# Button_Sequencer_single.net
KiCad netlist of a schematic drawn in EAGLE
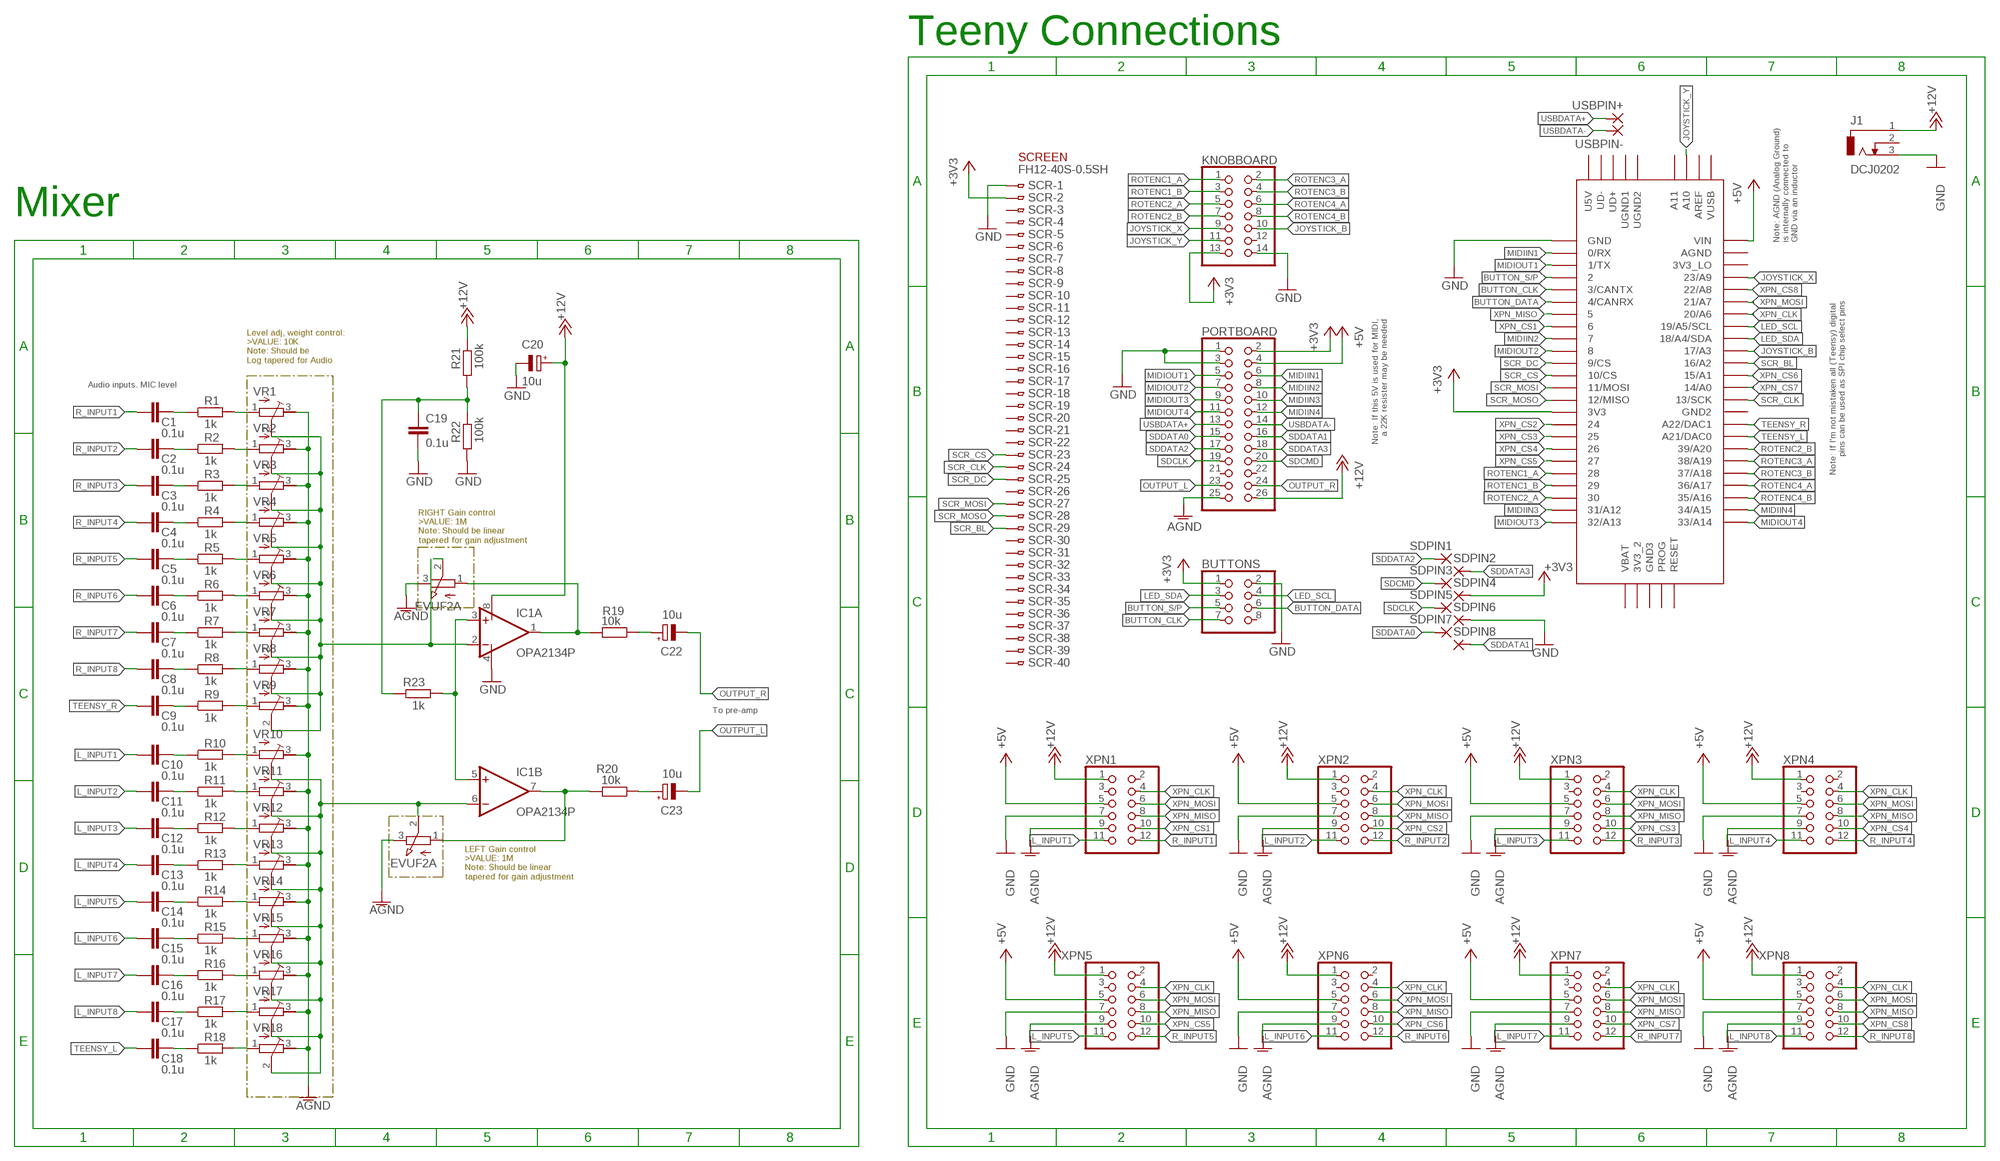
[diagram p0: schematic, sheet 1]

(export (version "E")
  (design (tool "Eeschema 10.0.6"))
  (components
    (comp (ref "BUTTONS")
      (value "PINHD-2X4")
      (footprint "eagle-import:2X04")
      (libsource (lib "eagle-import") (part "PINHD-2X4"))
    )
    (comp (ref "C1")
      (value "0.1u")
      (footprint "eagle-import:C025-030X050")
      (libsource (lib "eagle-import") (part "C-EU025-030X050"))
    )
    (comp (ref "C2")
      (value "0.1u")
      (footprint "eagle-import:C025-030X050")
      (libsource (lib "eagle-import") (part "C-EU025-030X050"))
    )
    (comp (ref "C3")
      (value "0.1u")
      (footprint "eagle-import:C025-030X050")
      (libsource (lib "eagle-import") (part "C-EU025-030X050"))
    )
    (comp (ref "C4")
      (value "0.1u")
      (footprint "eagle-import:C025-030X050")
      (libsource (lib "eagle-import") (part "C-EU025-030X050"))
    )
    (comp (ref "C5")
      (value "0.1u")
      (footprint "eagle-import:C025-030X050")
      (libsource (lib "eagle-import") (part "C-EU025-030X050"))
    )
    (comp (ref "C6")
      (value "0.1u")
      (footprint "eagle-import:C025-030X050")
      (libsource (lib "eagle-import") (part "C-EU025-030X050"))
    )
    (comp (ref "C7")
      (value "0.1u")
      (footprint "eagle-import:C025-030X050")
      (libsource (lib "eagle-import") (part "C-EU025-030X050"))
    )
    (comp (ref "C8")
      (value "0.1u")
      (footprint "eagle-import:C025-030X050")
      (libsource (lib "eagle-import") (part "C-EU025-030X050"))
    )
    (comp (ref "C9")
      (value "0.1u")
      (footprint "eagle-import:C025-030X050")
      (libsource (lib "eagle-import") (part "C-EU025-030X050"))
    )
    (comp (ref "C10")
      (value "0.1u")
      (footprint "eagle-import:C025-030X050")
      (libsource (lib "eagle-import") (part "C-EU025-030X050"))
    )
    (comp (ref "C11")
      (value "0.1u")
      (footprint "eagle-import:C025-030X050")
      (libsource (lib "eagle-import") (part "C-EU025-030X050"))
    )
    (comp (ref "C12")
      (value "0.1u")
      (footprint "eagle-import:C025-030X050")
      (libsource (lib "eagle-import") (part "C-EU025-030X050"))
    )
    (comp (ref "C13")
      (value "0.1u")
      (footprint "eagle-import:C025-030X050")
      (libsource (lib "eagle-import") (part "C-EU025-030X050"))
    )
    (comp (ref "C14")
      (value "0.1u")
      (footprint "eagle-import:C025-030X050")
      (libsource (lib "eagle-import") (part "C-EU025-030X050"))
    )
    (comp (ref "C15")
      (value "0.1u")
      (footprint "eagle-import:C025-030X050")
      (libsource (lib "eagle-import") (part "C-EU025-030X050"))
    )
    (comp (ref "C16")
      (value "0.1u")
      (footprint "eagle-import:C025-030X050")
      (libsource (lib "eagle-import") (part "C-EU025-030X050"))
    )
    (comp (ref "C17")
      (value "0.1u")
      (footprint "eagle-import:C025-030X050")
      (libsource (lib "eagle-import") (part "C-EU025-030X050"))
    )
    (comp (ref "C18")
      (value "0.1u")
      (footprint "eagle-import:C025-030X050")
      (libsource (lib "eagle-import") (part "C-EU025-030X050"))
    )
    (comp (ref "C19")
      (value "0.1u")
      (footprint "eagle-import:C0805")
      (libsource (lib "eagle-import") (part "C-EUC0805"))
    )
    (comp (ref "C20")
      (value "10u")
      (footprint "eagle-import:E5-10,5")
      (libsource (lib "eagle-import") (part "CPOL-EUE5-10.5"))
    )
    (comp (ref "C22")
      (value "10u")
      (footprint "eagle-import:E5-10,5")
      (libsource (lib "eagle-import") (part "CPOL-EUE5-10.5"))
    )
    (comp (ref "C23")
      (value "10u")
      (footprint "eagle-import:E5-10,5")
      (libsource (lib "eagle-import") (part "CPOL-EUE5-10.5"))
    )
    (comp (ref "IC1")
      (value "OPA2134P")
      (footprint "eagle-import:DIL08")
      (libsource (lib "eagle-import") (part "OPA2134P"))
    )
    (comp (ref "J1")
      (value "DCJ0202")
      (footprint "eagle-import:DCJ0202")
      (libsource (lib "eagle-import") (part "DCJ0202"))
    )
    (comp (ref "KNOBBOARD")
      (value "PINHD-2X7")
      (footprint "eagle-import:2X07")
      (libsource (lib "eagle-import") (part "PINHD-2X7"))
    )
    (comp (ref "PORTBOARD")
      (value "PINHD-2X13")
      (footprint "eagle-import:2X13")
      (libsource (lib "eagle-import") (part "PINHD-2X13"))
    )
    (comp (ref "R1")
      (value "1k")
      (footprint "eagle-import:R0805")
      (libsource (lib "eagle-import") (part "R-EU_R0805"))
    )
    (comp (ref "R2")
      (value "1k")
      (footprint "eagle-import:R0805")
      (libsource (lib "eagle-import") (part "R-EU_R0805"))
    )
    (comp (ref "R3")
      (value "1k")
      (footprint "eagle-import:R0805")
      (libsource (lib "eagle-import") (part "R-EU_R0805"))
    )
    (comp (ref "R4")
      (value "1k")
      (footprint "eagle-import:R0805")
      (libsource (lib "eagle-import") (part "R-EU_R0805"))
    )
    (comp (ref "R5")
      (value "1k")
      (footprint "eagle-import:R0805")
      (libsource (lib "eagle-import") (part "R-EU_R0805"))
    )
    (comp (ref "R6")
      (value "1k")
      (footprint "eagle-import:R0805")
      (libsource (lib "eagle-import") (part "R-EU_R0805"))
    )
    (comp (ref "R7")
      (value "1k")
      (footprint "eagle-import:R0805")
      (libsource (lib "eagle-import") (part "R-EU_R0805"))
    )
    (comp (ref "R8")
      (value "1k")
      (footprint "eagle-import:R0805")
      (libsource (lib "eagle-import") (part "R-EU_R0805"))
    )
    (comp (ref "R9")
      (value "1k")
      (footprint "eagle-import:R0805")
      (libsource (lib "eagle-import") (part "R-EU_R0805"))
    )
    (comp (ref "R10")
      (value "1k")
      (footprint "eagle-import:R0805")
      (libsource (lib "eagle-import") (part "R-EU_R0805"))
    )
    (comp (ref "R11")
      (value "1k")
      (footprint "eagle-import:R0805")
      (libsource (lib "eagle-import") (part "R-EU_R0805"))
    )
    (comp (ref "R12")
      (value "1k")
      (footprint "eagle-import:R0805")
      (libsource (lib "eagle-import") (part "R-EU_R0805"))
    )
    (comp (ref "R13")
      (value "1k")
      (footprint "eagle-import:R0805")
      (libsource (lib "eagle-import") (part "R-EU_R0805"))
    )
    (comp (ref "R14")
      (value "1k")
      (footprint "eagle-import:R0805")
      (libsource (lib "eagle-import") (part "R-EU_R0805"))
    )
    (comp (ref "R15")
      (value "1k")
      (footprint "eagle-import:R0805")
      (libsource (lib "eagle-import") (part "R-EU_R0805"))
    )
    (comp (ref "R16")
      (value "1k")
      (footprint "eagle-import:R0805")
      (libsource (lib "eagle-import") (part "R-EU_R0805"))
    )
    (comp (ref "R17")
      (value "1k")
      (footprint "eagle-import:R0805")
      (libsource (lib "eagle-import") (part "R-EU_R0805"))
    )
    (comp (ref "R18")
      (value "1k")
      (footprint "eagle-import:R0805")
      (libsource (lib "eagle-import") (part "R-EU_R0805"))
    )
    (comp (ref "R19")
      (value "10k")
      (footprint "eagle-import:R0805")
      (libsource (lib "eagle-import") (part "R-EU_R0805"))
    )
    (comp (ref "R20")
      (value "10k")
      (footprint "eagle-import:R0805")
      (libsource (lib "eagle-import") (part "R-EU_R0805"))
    )
    (comp (ref "R21")
      (value "100k")
      (footprint "eagle-import:R0805")
      (libsource (lib "eagle-import") (part "R-EU_R0805"))
    )
    (comp (ref "R22")
      (value "100k")
      (footprint "eagle-import:R0805")
      (libsource (lib "eagle-import") (part "R-EU_R0805"))
    )
    (comp (ref "R23")
      (value "1k")
      (footprint "eagle-import:R0805")
      (libsource (lib "eagle-import") (part "R-EU_R0805"))
    )
    (comp (ref "SCR")
      (value "FH12-40S-0.5SH")
      (footprint "eagle-import:FH12-40S-0.5SH")
      (fields (field (name "MPN") "FH12-40S-0.5SH(55)"))
      (libsource (lib "eagle-import") (part "FH12-40S-0.5SH"))
    )
    (comp (ref "SDPIN1")
      (value "1,6/0,8")
      (footprint "eagle-import:1,6_0,8")
      (libsource (lib "eagle-import") (part "1,6/0,8"))
    )
    (comp (ref "SDPIN2")
      (value "1,6/0,8")
      (footprint "eagle-import:1,6_0,8")
      (libsource (lib "eagle-import") (part "1,6/0,8"))
    )
    (comp (ref "SDPIN3")
      (value "1,6/0,8")
      (footprint "eagle-import:1,6_0,8")
      (libsource (lib "eagle-import") (part "1,6/0,8"))
    )
    (comp (ref "SDPIN4")
      (value "1,6/0,8")
      (footprint "eagle-import:1,6_0,8")
      (libsource (lib "eagle-import") (part "1,6/0,8"))
    )
    (comp (ref "SDPIN5")
      (value "1,6/0,8")
      (footprint "eagle-import:1,6_0,8")
      (libsource (lib "eagle-import") (part "1,6/0,8"))
    )
    (comp (ref "SDPIN6")
      (value "1,6/0,8")
      (footprint "eagle-import:1,6_0,8")
      (libsource (lib "eagle-import") (part "1,6/0,8"))
    )
    (comp (ref "SDPIN7")
      (value "1,6/0,8")
      (footprint "eagle-import:1,6_0,8")
      (libsource (lib "eagle-import") (part "1,6/0,8"))
    )
    (comp (ref "SDPIN8")
      (value "1,6/0,8")
      (footprint "eagle-import:1,6_0,8")
      (libsource (lib "eagle-import") (part "1,6/0,8"))
    )
    (comp (ref "TEENSY_3.6")
      (value "TEENSY_3.5/3.6")
      (footprint "eagle-import:TEENSY_3.5_3.6")
      (libsource (lib "eagle-import") (part "TEENSY_3.5/3.6"))
    )
    (comp (ref "USBPIN+")
      (value "1,6/0,8")
      (footprint "eagle-import:1,6_0,8")
      (libsource (lib "eagle-import") (part "1,6/0,8"))
    )
    (comp (ref "USBPIN-")
      (value "1,6/0,8")
      (footprint "eagle-import:1,6_0,8")
      (libsource (lib "eagle-import") (part "1,6/0,8"))
    )
    (comp (ref "VR1")
      (value "R-TRIMM3339P")
      (footprint "eagle-import:RTRIM3339P")
      (libsource (lib "eagle-import") (part "R-TRIMM3339P"))
    )
    (comp (ref "VR2")
      (value "R-TRIMM3339P")
      (footprint "eagle-import:RTRIM3339P")
      (libsource (lib "eagle-import") (part "R-TRIMM3339P"))
    )
    (comp (ref "VR3")
      (value "R-TRIMM3339P")
      (footprint "eagle-import:RTRIM3339P")
      (libsource (lib "eagle-import") (part "R-TRIMM3339P"))
    )
    (comp (ref "VR4")
      (value "R-TRIMM3339P")
      (footprint "eagle-import:RTRIM3339P")
      (libsource (lib "eagle-import") (part "R-TRIMM3339P"))
    )
    (comp (ref "VR5")
      (value "R-TRIMM3339P")
      (footprint "eagle-import:RTRIM3339P")
      (libsource (lib "eagle-import") (part "R-TRIMM3339P"))
    )
    (comp (ref "VR6")
      (value "R-TRIMM3339P")
      (footprint "eagle-import:RTRIM3339P")
      (libsource (lib "eagle-import") (part "R-TRIMM3339P"))
    )
    (comp (ref "VR7")
      (value "R-TRIMM3339P")
      (footprint "eagle-import:RTRIM3339P")
      (libsource (lib "eagle-import") (part "R-TRIMM3339P"))
    )
    (comp (ref "VR8")
      (value "R-TRIMM3339P")
      (footprint "eagle-import:RTRIM3339P")
      (libsource (lib "eagle-import") (part "R-TRIMM3339P"))
    )
    (comp (ref "VR9")
      (value "R-TRIMM3339P")
      (footprint "eagle-import:RTRIM3339P")
      (libsource (lib "eagle-import") (part "R-TRIMM3339P"))
    )
    (comp (ref "VR10")
      (value "R-TRIMM3339P")
      (footprint "eagle-import:RTRIM3339P")
      (libsource (lib "eagle-import") (part "R-TRIMM3339P"))
    )
    (comp (ref "VR11")
      (value "R-TRIMM3339P")
      (footprint "eagle-import:RTRIM3339P")
      (libsource (lib "eagle-import") (part "R-TRIMM3339P"))
    )
    (comp (ref "VR12")
      (value "R-TRIMM3339P")
      (footprint "eagle-import:RTRIM3339P")
      (libsource (lib "eagle-import") (part "R-TRIMM3339P"))
    )
    (comp (ref "VR13")
      (value "R-TRIMM3339P")
      (footprint "eagle-import:RTRIM3339P")
      (libsource (lib "eagle-import") (part "R-TRIMM3339P"))
    )
    (comp (ref "VR14")
      (value "R-TRIMM3339P")
      (footprint "eagle-import:RTRIM3339P")
      (libsource (lib "eagle-import") (part "R-TRIMM3339P"))
    )
    (comp (ref "VR15")
      (value "R-TRIMM3339P")
      (footprint "eagle-import:RTRIM3339P")
      (libsource (lib "eagle-import") (part "R-TRIMM3339P"))
    )
    (comp (ref "VR16")
      (value "R-TRIMM3339P")
      (footprint "eagle-import:RTRIM3339P")
      (libsource (lib "eagle-import") (part "R-TRIMM3339P"))
    )
    (comp (ref "VR17")
      (value "R-TRIMM3339P")
      (footprint "eagle-import:RTRIM3339P")
      (libsource (lib "eagle-import") (part "R-TRIMM3339P"))
    )
    (comp (ref "VR18")
      (value "R-TRIMM3339P")
      (footprint "eagle-import:RTRIM3339P")
      (libsource (lib "eagle-import") (part "R-TRIMM3339P"))
    )
    (comp (ref "VR19")
      (value "EVUF2A")
      (footprint "eagle-import:EVUF")
      (libsource (lib "eagle-import") (part "EVUAF2"))
    )
    (comp (ref "VR20")
      (value "EVUF2A")
      (footprint "eagle-import:EVUF")
      (libsource (lib "eagle-import") (part "EVUAF2"))
    )
    (comp (ref "XPN1")
      (value "PINHD-2X6")
      (footprint "eagle-import:2X06")
      (libsource (lib "eagle-import") (part "PINHD-2X6"))
    )
    (comp (ref "XPN2")
      (value "PINHD-2X6")
      (footprint "eagle-import:2X06")
      (libsource (lib "eagle-import") (part "PINHD-2X6"))
    )
    (comp (ref "XPN3")
      (value "PINHD-2X6")
      (footprint "eagle-import:2X06")
      (libsource (lib "eagle-import") (part "PINHD-2X6"))
    )
    (comp (ref "XPN4")
      (value "PINHD-2X6")
      (footprint "eagle-import:2X06")
      (libsource (lib "eagle-import") (part "PINHD-2X6"))
    )
    (comp (ref "XPN5")
      (value "PINHD-2X6")
      (footprint "eagle-import:2X06")
      (libsource (lib "eagle-import") (part "PINHD-2X6"))
    )
    (comp (ref "XPN6")
      (value "PINHD-2X6")
      (footprint "eagle-import:2X06")
      (libsource (lib "eagle-import") (part "PINHD-2X6"))
    )
    (comp (ref "XPN7")
      (value "PINHD-2X6")
      (footprint "eagle-import:2X06")
      (libsource (lib "eagle-import") (part "PINHD-2X6"))
    )
    (comp (ref "XPN8")
      (value "PINHD-2X6")
      (footprint "eagle-import:2X06")
      (libsource (lib "eagle-import") (part "PINHD-2X6"))
    )
  )
  (nets
    (net (code "1") (name "+3V3") (class "Default")
      (node (ref "BUTTONS") (pin "1") (pinfunction "1_1") (pintype "passive"))
      (node (ref "KNOBBOARD") (pin "13") (pinfunction "13_13") (pintype "passive"))
      (node (ref "PORTBOARD") (pin "2") (pinfunction "2_2") (pintype "passive"))
      (node (ref "SCR") (pin "2") (pinfunction "1_2") (pintype "passive"))
      (node (ref "SDPIN4") (pin "1") (pinfunction "P_1") (pintype "passive"))
      (node (ref "TEENSY_3.6") (pin "3V3") (pinfunction "3V3_3V3") (pintype "bidirectional"))
    )
    (net (code "2") (name "+5V") (class "Default")
      (node (ref "PORTBOARD") (pin "4") (pinfunction "4_4") (pintype "passive"))
      (node (ref "TEENSY_3.6") (pin "VIN") (pinfunction "VIN_VIN") (pintype "bidirectional"))
      (node (ref "XPN1") (pin "5") (pinfunction "5_5") (pintype "passive"))
      (node (ref "XPN2") (pin "5") (pinfunction "5_5") (pintype "passive"))
      (node (ref "XPN3") (pin "5") (pinfunction "5_5") (pintype "passive"))
      (node (ref "XPN4") (pin "5") (pinfunction "5_5") (pintype "passive"))
      (node (ref "XPN5") (pin "5") (pinfunction "5_5") (pintype "passive"))
      (node (ref "XPN6") (pin "5") (pinfunction "5_5") (pintype "passive"))
      (node (ref "XPN7") (pin "5") (pinfunction "5_5") (pintype "passive"))
      (node (ref "XPN8") (pin "5") (pinfunction "5_5") (pintype "passive"))
    )
    (net (code "3") (name "+12V") (class "Default")
      (node (ref "C20") (pin "+") (pinfunction "+_+") (pintype "passive"))
      (node (ref "IC1") (pin "8") (pinfunction "V+_8") (pintype "power_in"))
      (node (ref "J1") (pin "1") (pinfunction "1_1") (pintype "passive"))
      (node (ref "PORTBOARD") (pin "26") (pinfunction "26_26") (pintype "passive"))
      (node (ref "R21") (pin "2") (pinfunction "2_2") (pintype "passive"))
      (node (ref "XPN1") (pin "1") (pinfunction "1_1") (pintype "passive"))
      (node (ref "XPN2") (pin "1") (pinfunction "1_1") (pintype "passive"))
      (node (ref "XPN3") (pin "1") (pinfunction "1_1") (pintype "passive"))
      (node (ref "XPN4") (pin "1") (pinfunction "1_1") (pintype "passive"))
      (node (ref "XPN5") (pin "1") (pinfunction "1_1") (pintype "passive"))
      (node (ref "XPN6") (pin "1") (pinfunction "1_1") (pintype "passive"))
      (node (ref "XPN7") (pin "1") (pinfunction "1_1") (pintype "passive"))
      (node (ref "XPN8") (pin "1") (pinfunction "1_1") (pintype "passive"))
    )
    (net (code "4") (name "AGND") (class "Default")
      (node (ref "PORTBOARD") (pin "25") (pinfunction "25_25") (pintype "passive"))
      (node (ref "VR1") (pin "3") (pinfunction "E_3") (pintype "passive"))
      (node (ref "VR10") (pin "3") (pinfunction "E_3") (pintype "passive"))
      (node (ref "VR11") (pin "3") (pinfunction "E_3") (pintype "passive"))
      (node (ref "VR12") (pin "3") (pinfunction "E_3") (pintype "passive"))
      (node (ref "VR13") (pin "3") (pinfunction "E_3") (pintype "passive"))
      (node (ref "VR14") (pin "3") (pinfunction "E_3") (pintype "passive"))
      (node (ref "VR15") (pin "3") (pinfunction "E_3") (pintype "passive"))
      (node (ref "VR16") (pin "3") (pinfunction "E_3") (pintype "passive"))
      (node (ref "VR17") (pin "3") (pinfunction "E_3") (pintype "passive"))
      (node (ref "VR18") (pin "3") (pinfunction "E_3") (pintype "passive"))
      (node (ref "VR19") (pin "3") (pinfunction "E_3") (pintype "passive"))
      (node (ref "VR2") (pin "3") (pinfunction "E_3") (pintype "passive"))
      (node (ref "VR20") (pin "3") (pinfunction "E_3") (pintype "passive"))
      (node (ref "VR3") (pin "3") (pinfunction "E_3") (pintype "passive"))
      (node (ref "VR4") (pin "3") (pinfunction "E_3") (pintype "passive"))
      (node (ref "VR5") (pin "3") (pinfunction "E_3") (pintype "passive"))
      (node (ref "VR6") (pin "3") (pinfunction "E_3") (pintype "passive"))
      (node (ref "VR7") (pin "3") (pinfunction "E_3") (pintype "passive"))
      (node (ref "VR8") (pin "3") (pinfunction "E_3") (pintype "passive"))
      (node (ref "VR9") (pin "3") (pinfunction "E_3") (pintype "passive"))
      (node (ref "XPN1") (pin "9") (pinfunction "9_9") (pintype "passive"))
      (node (ref "XPN2") (pin "9") (pinfunction "9_9") (pintype "passive"))
      (node (ref "XPN3") (pin "9") (pinfunction "9_9") (pintype "passive"))
      (node (ref "XPN4") (pin "9") (pinfunction "9_9") (pintype "passive"))
      (node (ref "XPN5") (pin "9") (pinfunction "9_9") (pintype "passive"))
      (node (ref "XPN6") (pin "9") (pinfunction "9_9") (pintype "passive"))
      (node (ref "XPN7") (pin "9") (pinfunction "9_9") (pintype "passive"))
      (node (ref "XPN8") (pin "9") (pinfunction "9_9") (pintype "passive"))
    )
    (net (code "5") (name "BUTTON_CLK") (class "Default")
      (node (ref "BUTTONS") (pin "7") (pinfunction "7_7") (pintype "passive"))
      (node (ref "TEENSY_3.6") (pin "3/CANTX") (pinfunction "3/CANTX_3/CANTX") (pintype "bidirectional"))
    )
    (net (code "6") (name "BUTTON_DATA") (class "Default")
      (node (ref "BUTTONS") (pin "6") (pinfunction "6_6") (pintype "passive"))
      (node (ref "TEENSY_3.6") (pin "4/CANRX") (pinfunction "4/CANRX_4/CANRX") (pintype "bidirectional"))
    )
    (net (code "7") (name "BUTTON_S{slash}P") (class "Default")
      (node (ref "BUTTONS") (pin "5") (pinfunction "5_5") (pintype "passive"))
      (node (ref "TEENSY_3.6") (pin "2") (pinfunction "2_2") (pintype "bidirectional"))
    )
    (net (code "8") (name "GND") (class "Default")
      (node (ref "BUTTONS") (pin "2") (pinfunction "2_2") (pintype "passive"))
      (node (ref "C19") (pin "2") (pinfunction "2_2") (pintype "passive"))
      (node (ref "C20") (pin "-") (pinfunction "-_-") (pintype "passive"))
      (node (ref "IC1") (pin "4") (pinfunction "V-_4") (pintype "power_in"))
      (node (ref "J1") (pin "3") (pinfunction "3_3") (pintype "passive"))
      (node (ref "KNOBBOARD") (pin "14") (pinfunction "14_14") (pintype "passive"))
      (node (ref "PORTBOARD") (pin "1") (pinfunction "1_1") (pintype "passive"))
      (node (ref "PORTBOARD") (pin "3") (pinfunction "3_3") (pintype "passive"))
      (node (ref "R22") (pin "1") (pinfunction "1_1") (pintype "passive"))
      (node (ref "SCR") (pin "1") (pinfunction "1_1") (pintype "passive"))
      (node (ref "SDPIN6") (pin "1") (pinfunction "P_1") (pintype "passive"))
      (node (ref "TEENSY_3.6") (pin "GND") (pinfunction "GND_GND") (pintype "bidirectional"))
      (node (ref "XPN1") (pin "7") (pinfunction "7_7") (pintype "passive"))
      (node (ref "XPN2") (pin "7") (pinfunction "7_7") (pintype "passive"))
      (node (ref "XPN3") (pin "7") (pinfunction "7_7") (pintype "passive"))
      (node (ref "XPN4") (pin "7") (pinfunction "7_7") (pintype "passive"))
      (node (ref "XPN5") (pin "7") (pinfunction "7_7") (pintype "passive"))
      (node (ref "XPN6") (pin "7") (pinfunction "7_7") (pintype "passive"))
      (node (ref "XPN7") (pin "7") (pinfunction "7_7") (pintype "passive"))
      (node (ref "XPN8") (pin "7") (pinfunction "7_7") (pintype "passive"))
    )
    (net (code "9") (name "JOYSTICK_B") (class "Default")
      (node (ref "KNOBBOARD") (pin "10") (pinfunction "10_10") (pintype "passive"))
      (node (ref "TEENSY_3.6") (pin "17/A3") (pinfunction "17/A3_17/A3") (pintype "bidirectional"))
    )
    (net (code "10") (name "JOYSTICK_X") (class "Default")
      (node (ref "KNOBBOARD") (pin "9") (pinfunction "9_9") (pintype "passive"))
      (node (ref "TEENSY_3.6") (pin "23/A9") (pinfunction "23/A9_23/A9") (pintype "bidirectional"))
    )
    (net (code "11") (name "JOYSTICK_Y") (class "Default")
      (node (ref "KNOBBOARD") (pin "11") (pinfunction "11_11") (pintype "passive"))
      (node (ref "TEENSY_3.6") (pin "A10") (pinfunction "A10_A10") (pintype "bidirectional"))
    )
    (net (code "12") (name "LED_SCL") (class "Default")
      (node (ref "BUTTONS") (pin "4") (pinfunction "4_4") (pintype "passive"))
      (node (ref "TEENSY_3.6") (pin "19/A5/SCL") (pinfunction "19/A5/SCL_19/A5/SCL") (pintype "bidirectional"))
    )
    (net (code "13") (name "LED_SDA") (class "Default")
      (node (ref "BUTTONS") (pin "3") (pinfunction "3_3") (pintype "passive"))
      (node (ref "TEENSY_3.6") (pin "18/A4/SDA") (pinfunction "18/A4/SDA_18/A4/SDA") (pintype "bidirectional"))
    )
    (net (code "14") (name "L_INPUT1") (class "Default")
      (node (ref "C10") (pin "2") (pinfunction "2_2") (pintype "passive"))
      (node (ref "XPN1") (pin "11") (pinfunction "11_11") (pintype "passive"))
    )
    (net (code "15") (name "L_INPUT2") (class "Default")
      (node (ref "C11") (pin "2") (pinfunction "2_2") (pintype "passive"))
      (node (ref "XPN2") (pin "11") (pinfunction "11_11") (pintype "passive"))
    )
    (net (code "16") (name "L_INPUT3") (class "Default")
      (node (ref "C12") (pin "2") (pinfunction "2_2") (pintype "passive"))
      (node (ref "XPN3") (pin "11") (pinfunction "11_11") (pintype "passive"))
    )
    (net (code "17") (name "L_INPUT4") (class "Default")
      (node (ref "C13") (pin "2") (pinfunction "2_2") (pintype "passive"))
      (node (ref "XPN4") (pin "11") (pinfunction "11_11") (pintype "passive"))
    )
    (net (code "18") (name "L_INPUT5") (class "Default")
      (node (ref "C14") (pin "2") (pinfunction "2_2") (pintype "passive"))
      (node (ref "XPN5") (pin "11") (pinfunction "11_11") (pintype "passive"))
    )
    (net (code "19") (name "L_INPUT6") (class "Default")
      (node (ref "C15") (pin "2") (pinfunction "2_2") (pintype "passive"))
      (node (ref "XPN6") (pin "11") (pinfunction "11_11") (pintype "passive"))
    )
    (net (code "20") (name "L_INPUT7") (class "Default")
      (node (ref "C16") (pin "2") (pinfunction "2_2") (pintype "passive"))
      (node (ref "XPN7") (pin "11") (pinfunction "11_11") (pintype "passive"))
    )
    (net (code "21") (name "L_INPUT8") (class "Default")
      (node (ref "C17") (pin "2") (pinfunction "2_2") (pintype "passive"))
      (node (ref "XPN8") (pin "11") (pinfunction "11_11") (pintype "passive"))
    )
    (net (code "22") (name "MIDIIN1") (class "Default")
      (node (ref "PORTBOARD") (pin "6") (pinfunction "6_6") (pintype "passive"))
      (node (ref "TEENSY_3.6") (pin "0/RX") (pinfunction "0/RX_0/RX") (pintype "bidirectional"))
    )
    (net (code "23") (name "MIDIIN2") (class "Default")
      (node (ref "PORTBOARD") (pin "8") (pinfunction "8_8") (pintype "passive"))
      (node (ref "TEENSY_3.6") (pin "7") (pinfunction "7_7") (pintype "bidirectional"))
    )
    (net (code "24") (name "MIDIIN3") (class "Default")
      (node (ref "PORTBOARD") (pin "10") (pinfunction "10_10") (pintype "passive"))
      (node (ref "TEENSY_3.6") (pin "31/A12") (pinfunction "31/A12_31/A12") (pintype "bidirectional"))
    )
    (net (code "25") (name "MIDIIN4") (class "Default")
      (node (ref "PORTBOARD") (pin "12") (pinfunction "12_12") (pintype "passive"))
      (node (ref "TEENSY_3.6") (pin "34/A15") (pinfunction "34/A15_34/A15") (pintype "bidirectional"))
    )
    (net (code "26") (name "MIDIOUT1") (class "Default")
      (node (ref "PORTBOARD") (pin "5") (pinfunction "5_5") (pintype "passive"))
      (node (ref "TEENSY_3.6") (pin "1/TX") (pinfunction "1/TX_1/TX") (pintype "bidirectional"))
    )
    (net (code "27") (name "MIDIOUT2") (class "Default")
      (node (ref "PORTBOARD") (pin "7") (pinfunction "7_7") (pintype "passive"))
      (node (ref "TEENSY_3.6") (pin "8") (pinfunction "8_8") (pintype "bidirectional"))
    )
    (net (code "28") (name "MIDIOUT3") (class "Default")
      (node (ref "PORTBOARD") (pin "9") (pinfunction "9_9") (pintype "passive"))
      (node (ref "TEENSY_3.6") (pin "32/A13") (pinfunction "32/A13_32/A13") (pintype "bidirectional"))
    )
    (net (code "29") (name "MIDIOUT4") (class "Default")
      (node (ref "PORTBOARD") (pin "11") (pinfunction "11_11") (pintype "passive"))
      (node (ref "TEENSY_3.6") (pin "33/A14") (pinfunction "33/A14_33/A14") (pintype "bidirectional"))
    )
    (net (code "30") (name "Net-(C1-Pad1)") (class "Default")
      (node (ref "C1") (pin "1") (pinfunction "1_1") (pintype "passive"))
      (node (ref "R1") (pin "1") (pinfunction "1_1") (pintype "passive"))
    )
    (net (code "31") (name "Net-(C2-Pad1)") (class "Default")
      (node (ref "C2") (pin "1") (pinfunction "1_1") (pintype "passive"))
      (node (ref "R2") (pin "1") (pinfunction "1_1") (pintype "passive"))
    )
    (net (code "32") (name "Net-(C3-Pad1)") (class "Default")
      (node (ref "C3") (pin "1") (pinfunction "1_1") (pintype "passive"))
      (node (ref "R3") (pin "1") (pinfunction "1_1") (pintype "passive"))
    )
    (net (code "33") (name "Net-(C4-Pad1)") (class "Default")
      (node (ref "C4") (pin "1") (pinfunction "1_1") (pintype "passive"))
      (node (ref "R4") (pin "1") (pinfunction "1_1") (pintype "passive"))
    )
    (net (code "34") (name "Net-(C5-Pad1)") (class "Default")
      (node (ref "C5") (pin "1") (pinfunction "1_1") (pintype "passive"))
      (node (ref "R5") (pin "1") (pinfunction "1_1") (pintype "passive"))
    )
    (net (code "35") (name "Net-(C6-Pad1)") (class "Default")
      (node (ref "C6") (pin "1") (pinfunction "1_1") (pintype "passive"))
      (node (ref "R6") (pin "1") (pinfunction "1_1") (pintype "passive"))
    )
    (net (code "36") (name "Net-(C7-Pad1)") (class "Default")
      (node (ref "C7") (pin "1") (pinfunction "1_1") (pintype "passive"))
      (node (ref "R7") (pin "1") (pinfunction "1_1") (pintype "passive"))
    )
    (net (code "37") (name "Net-(C8-Pad1)") (class "Default")
      (node (ref "C8") (pin "1") (pinfunction "1_1") (pintype "passive"))
      (node (ref "R8") (pin "1") (pinfunction "1_1") (pintype "passive"))
    )
    (net (code "38") (name "Net-(C9-Pad1)") (class "Default")
      (node (ref "C9") (pin "1") (pinfunction "1_1") (pintype "passive"))
      (node (ref "R9") (pin "1") (pinfunction "1_1") (pintype "passive"))
    )
    (net (code "39") (name "Net-(C10-Pad1)") (class "Default")
      (node (ref "C10") (pin "1") (pinfunction "1_1") (pintype "passive"))
      (node (ref "R10") (pin "1") (pinfunction "1_1") (pintype "passive"))
    )
    (net (code "40") (name "Net-(C11-Pad1)") (class "Default")
      (node (ref "C11") (pin "1") (pinfunction "1_1") (pintype "passive"))
      (node (ref "R11") (pin "1") (pinfunction "1_1") (pintype "passive"))
    )
    (net (code "41") (name "Net-(C12-Pad1)") (class "Default")
      (node (ref "C12") (pin "1") (pinfunction "1_1") (pintype "passive"))
      (node (ref "R12") (pin "1") (pinfunction "1_1") (pintype "passive"))
    )
    (net (code "42") (name "Net-(C13-Pad1)") (class "Default")
      (node (ref "C13") (pin "1") (pinfunction "1_1") (pintype "passive"))
      (node (ref "R13") (pin "1") (pinfunction "1_1") (pintype "passive"))
    )
    (net (code "43") (name "Net-(C14-Pad1)") (class "Default")
      (node (ref "C14") (pin "1") (pinfunction "1_1") (pintype "passive"))
      (node (ref "R14") (pin "1") (pinfunction "1_1") (pintype "passive"))
    )
    (net (code "44") (name "Net-(C15-Pad1)") (class "Default")
      (node (ref "C15") (pin "1") (pinfunction "1_1") (pintype "passive"))
      (node (ref "R15") (pin "1") (pinfunction "1_1") (pintype "passive"))
    )
    (net (code "45") (name "Net-(C16-Pad1)") (class "Default")
      (node (ref "C16") (pin "1") (pinfunction "1_1") (pintype "passive"))
      (node (ref "R16") (pin "1") (pinfunction "1_1") (pintype "passive"))
    )
    (net (code "46") (name "Net-(C17-Pad1)") (class "Default")
      (node (ref "C17") (pin "1") (pinfunction "1_1") (pintype "passive"))
      (node (ref "R17") (pin "1") (pinfunction "1_1") (pintype "passive"))
    )
    (net (code "47") (name "Net-(C18-Pad1)") (class "Default")
      (node (ref "C18") (pin "1") (pinfunction "1_1") (pintype "passive"))
      (node (ref "R18") (pin "1") (pinfunction "1_1") (pintype "passive"))
    )
    (net (code "48") (name "Net-(C19-Pad1)") (class "Default")
      (node (ref "C19") (pin "1") (pinfunction "1_1") (pintype "passive"))
      (node (ref "R21") (pin "1") (pinfunction "1_1") (pintype "passive"))
      (node (ref "R22") (pin "2") (pinfunction "2_2") (pintype "passive"))
      (node (ref "R23") (pin "2") (pinfunction "2_2") (pintype "passive"))
    )
    (net (code "49") (name "Net-(C22-Pad+)") (class "Default")
      (node (ref "C22") (pin "+") (pinfunction "+_+") (pintype "passive"))
      (node (ref "R19") (pin "1") (pinfunction "1_1") (pintype "passive"))
    )
    (net (code "50") (name "Net-(C23-Pad+)") (class "Default")
      (node (ref "C23") (pin "+") (pinfunction "+_+") (pintype "passive"))
      (node (ref "R20") (pin "1") (pinfunction "1_1") (pintype "passive"))
    )
    (net (code "51") (name "Net-(IC1A-+IN)") (class "Default")
      (node (ref "IC1") (pin "3") (pinfunction "+IN_3") (pintype "input"))
      (node (ref "IC1") (pin "5") (pinfunction "+IN_5") (pintype "input"))
      (node (ref "R23") (pin "1") (pinfunction "1_1") (pintype "passive"))
    )
    (net (code "52") (name "Net-(IC1A--IN)") (class "Default")
      (node (ref "IC1") (pin "2") (pinfunction "-IN_2") (pintype "input"))
      (node (ref "VR1") (pin "2") (pinfunction "S_2") (pintype "passive"))
      (node (ref "VR19") (pin "2") (pinfunction "S_2") (pintype "passive"))
      (node (ref "VR2") (pin "2") (pinfunction "S_2") (pintype "passive"))
      (node (ref "VR3") (pin "2") (pinfunction "S_2") (pintype "passive"))
      (node (ref "VR4") (pin "2") (pinfunction "S_2") (pintype "passive"))
      (node (ref "VR5") (pin "2") (pinfunction "S_2") (pintype "passive"))
      (node (ref "VR6") (pin "2") (pinfunction "S_2") (pintype "passive"))
      (node (ref "VR7") (pin "2") (pinfunction "S_2") (pintype "passive"))
      (node (ref "VR8") (pin "2") (pinfunction "S_2") (pintype "passive"))
      (node (ref "VR9") (pin "2") (pinfunction "S_2") (pintype "passive"))
    )
    (net (code "53") (name "Net-(IC1A-OUT)") (class "Default")
      (node (ref "IC1") (pin "1") (pinfunction "OUT_1") (pintype "output"))
      (node (ref "R19") (pin "2") (pinfunction "2_2") (pintype "passive"))
      (node (ref "VR19") (pin "1") (pinfunction "A_1") (pintype "passive"))
    )
    (net (code "54") (name "Net-(IC1B--IN)") (class "Default")
      (node (ref "IC1") (pin "6") (pinfunction "-IN_6") (pintype "input"))
      (node (ref "VR10") (pin "2") (pinfunction "S_2") (pintype "passive"))
      (node (ref "VR11") (pin "2") (pinfunction "S_2") (pintype "passive"))
      (node (ref "VR12") (pin "2") (pinfunction "S_2") (pintype "passive"))
      (node (ref "VR13") (pin "2") (pinfunction "S_2") (pintype "passive"))
      (node (ref "VR14") (pin "2") (pinfunction "S_2") (pintype "passive"))
      (node (ref "VR15") (pin "2") (pinfunction "S_2") (pintype "passive"))
      (node (ref "VR16") (pin "2") (pinfunction "S_2") (pintype "passive"))
      (node (ref "VR17") (pin "2") (pinfunction "S_2") (pintype "passive"))
      (node (ref "VR18") (pin "2") (pinfunction "S_2") (pintype "passive"))
      (node (ref "VR20") (pin "2") (pinfunction "S_2") (pintype "passive"))
    )
    (net (code "55") (name "Net-(IC1B-OUT)") (class "Default")
      (node (ref "IC1") (pin "7") (pinfunction "OUT_7") (pintype "output"))
      (node (ref "R20") (pin "2") (pinfunction "2_2") (pintype "passive"))
      (node (ref "VR20") (pin "1") (pinfunction "A_1") (pintype "passive"))
    )
    (net (code "56") (name "Net-(VR1-A)") (class "Default")
      (node (ref "R1") (pin "2") (pinfunction "2_2") (pintype "passive"))
      (node (ref "VR1") (pin "1") (pinfunction "A_1") (pintype "passive"))
    )
    (net (code "57") (name "Net-(VR2-A)") (class "Default")
      (node (ref "R2") (pin "2") (pinfunction "2_2") (pintype "passive"))
      (node (ref "VR2") (pin "1") (pinfunction "A_1") (pintype "passive"))
    )
    (net (code "58") (name "Net-(VR3-A)") (class "Default")
      (node (ref "R3") (pin "2") (pinfunction "2_2") (pintype "passive"))
      (node (ref "VR3") (pin "1") (pinfunction "A_1") (pintype "passive"))
    )
    (net (code "59") (name "Net-(VR4-A)") (class "Default")
      (node (ref "R4") (pin "2") (pinfunction "2_2") (pintype "passive"))
      (node (ref "VR4") (pin "1") (pinfunction "A_1") (pintype "passive"))
    )
    (net (code "60") (name "Net-(VR5-A)") (class "Default")
      (node (ref "R5") (pin "2") (pinfunction "2_2") (pintype "passive"))
      (node (ref "VR5") (pin "1") (pinfunction "A_1") (pintype "passive"))
    )
    (net (code "61") (name "Net-(VR6-A)") (class "Default")
      (node (ref "R6") (pin "2") (pinfunction "2_2") (pintype "passive"))
      (node (ref "VR6") (pin "1") (pinfunction "A_1") (pintype "passive"))
    )
    (net (code "62") (name "Net-(VR7-A)") (class "Default")
      (node (ref "R7") (pin "2") (pinfunction "2_2") (pintype "passive"))
      (node (ref "VR7") (pin "1") (pinfunction "A_1") (pintype "passive"))
    )
    (net (code "63") (name "Net-(VR8-A)") (class "Default")
      (node (ref "R8") (pin "2") (pinfunction "2_2") (pintype "passive"))
      (node (ref "VR8") (pin "1") (pinfunction "A_1") (pintype "passive"))
    )
    (net (code "64") (name "Net-(VR9-A)") (class "Default")
      (node (ref "R9") (pin "2") (pinfunction "2_2") (pintype "passive"))
      (node (ref "VR9") (pin "1") (pinfunction "A_1") (pintype "passive"))
    )
    (net (code "65") (name "Net-(VR10-A)") (class "Default")
      (node (ref "R10") (pin "2") (pinfunction "2_2") (pintype "passive"))
      (node (ref "VR10") (pin "1") (pinfunction "A_1") (pintype "passive"))
    )
    (net (code "66") (name "Net-(VR11-A)") (class "Default")
      (node (ref "R11") (pin "2") (pinfunction "2_2") (pintype "passive"))
      (node (ref "VR11") (pin "1") (pinfunction "A_1") (pintype "passive"))
    )
    (net (code "67") (name "Net-(VR12-A)") (class "Default")
      (node (ref "R12") (pin "2") (pinfunction "2_2") (pintype "passive"))
      (node (ref "VR12") (pin "1") (pinfunction "A_1") (pintype "passive"))
    )
    (net (code "68") (name "Net-(VR13-A)") (class "Default")
      (node (ref "R13") (pin "2") (pinfunction "2_2") (pintype "passive"))
      (node (ref "VR13") (pin "1") (pinfunction "A_1") (pintype "passive"))
    )
    (net (code "69") (name "Net-(VR14-A)") (class "Default")
      (node (ref "R14") (pin "2") (pinfunction "2_2") (pintype "passive"))
      (node (ref "VR14") (pin "1") (pinfunction "A_1") (pintype "passive"))
    )
    (net (code "70") (name "Net-(VR15-A)") (class "Default")
      (node (ref "R15") (pin "2") (pinfunction "2_2") (pintype "passive"))
      (node (ref "VR15") (pin "1") (pinfunction "A_1") (pintype "passive"))
    )
    (net (code "71") (name "Net-(VR16-A)") (class "Default")
      (node (ref "R16") (pin "2") (pinfunction "2_2") (pintype "passive"))
      (node (ref "VR16") (pin "1") (pinfunction "A_1") (pintype "passive"))
    )
    (net (code "72") (name "Net-(VR17-A)") (class "Default")
      (node (ref "R17") (pin "2") (pinfunction "2_2") (pintype "passive"))
      (node (ref "VR17") (pin "1") (pinfunction "A_1") (pintype "passive"))
    )
    (net (code "73") (name "Net-(VR18-A)") (class "Default")
      (node (ref "R18") (pin "2") (pinfunction "2_2") (pintype "passive"))
      (node (ref "VR18") (pin "1") (pinfunction "A_1") (pintype "passive"))
    )
    (net (code "74") (name "OUTPUT_L") (class "Default")
      (node (ref "C23") (pin "-") (pinfunction "-_-") (pintype "passive"))
      (node (ref "PORTBOARD") (pin "23") (pinfunction "23_23") (pintype "passive"))
    )
    (net (code "75") (name "OUTPUT_R") (class "Default")
      (node (ref "C22") (pin "-") (pinfunction "-_-") (pintype "passive"))
      (node (ref "PORTBOARD") (pin "24") (pinfunction "24_24") (pintype "passive"))
    )
    (net (code "76") (name "ROTENC1_A") (class "Default")
      (node (ref "KNOBBOARD") (pin "1") (pinfunction "1_1") (pintype "passive"))
      (node (ref "TEENSY_3.6") (pin "28") (pinfunction "28_28") (pintype "bidirectional"))
    )
    (net (code "77") (name "ROTENC1_B") (class "Default")
      (node (ref "KNOBBOARD") (pin "3") (pinfunction "3_3") (pintype "passive"))
      (node (ref "TEENSY_3.6") (pin "29") (pinfunction "29_29") (pintype "bidirectional"))
    )
    (net (code "78") (name "ROTENC2_A") (class "Default")
      (node (ref "KNOBBOARD") (pin "5") (pinfunction "5_5") (pintype "passive"))
      (node (ref "TEENSY_3.6") (pin "30") (pinfunction "30_30") (pintype "bidirectional"))
    )
    (net (code "79") (name "ROTENC2_B") (class "Default")
      (node (ref "KNOBBOARD") (pin "7") (pinfunction "7_7") (pintype "passive"))
      (node (ref "TEENSY_3.6") (pin "39/A20") (pinfunction "39/A20_39/A20") (pintype "bidirectional"))
    )
    (net (code "80") (name "ROTENC3_A") (class "Default")
      (node (ref "KNOBBOARD") (pin "2") (pinfunction "2_2") (pintype "passive"))
      (node (ref "TEENSY_3.6") (pin "38/A19") (pinfunction "38/A19_38/A19") (pintype "bidirectional"))
    )
    (net (code "81") (name "ROTENC3_B") (class "Default")
      (node (ref "KNOBBOARD") (pin "4") (pinfunction "4_4") (pintype "passive"))
      (node (ref "TEENSY_3.6") (pin "37/A18") (pinfunction "37/A18_37/A18") (pintype "bidirectional"))
    )
    (net (code "82") (name "ROTENC4_A") (class "Default")
      (node (ref "KNOBBOARD") (pin "6") (pinfunction "6_6") (pintype "passive"))
      (node (ref "TEENSY_3.6") (pin "36/A17") (pinfunction "36/A17_36/A17") (pintype "bidirectional"))
    )
    (net (code "83") (name "ROTENC4_B") (class "Default")
      (node (ref "KNOBBOARD") (pin "8") (pinfunction "8_8") (pintype "passive"))
      (node (ref "TEENSY_3.6") (pin "35/A16") (pinfunction "35/A16_35/A16") (pintype "bidirectional"))
    )
    (net (code "84") (name "R_INPUT1") (class "Default")
      (node (ref "C1") (pin "2") (pinfunction "2_2") (pintype "passive"))
      (node (ref "XPN1") (pin "12") (pinfunction "12_12") (pintype "passive"))
    )
    (net (code "85") (name "R_INPUT2") (class "Default")
      (node (ref "C2") (pin "2") (pinfunction "2_2") (pintype "passive"))
      (node (ref "XPN2") (pin "12") (pinfunction "12_12") (pintype "passive"))
    )
    (net (code "86") (name "R_INPUT3") (class "Default")
      (node (ref "C3") (pin "2") (pinfunction "2_2") (pintype "passive"))
      (node (ref "XPN3") (pin "12") (pinfunction "12_12") (pintype "passive"))
    )
    (net (code "87") (name "R_INPUT4") (class "Default")
      (node (ref "C4") (pin "2") (pinfunction "2_2") (pintype "passive"))
      (node (ref "XPN4") (pin "12") (pinfunction "12_12") (pintype "passive"))
    )
    (net (code "88") (name "R_INPUT5") (class "Default")
      (node (ref "C5") (pin "2") (pinfunction "2_2") (pintype "passive"))
      (node (ref "XPN5") (pin "12") (pinfunction "12_12") (pintype "passive"))
    )
    (net (code "89") (name "R_INPUT6") (class "Default")
      (node (ref "C6") (pin "2") (pinfunction "2_2") (pintype "passive"))
      (node (ref "XPN6") (pin "12") (pinfunction "12_12") (pintype "passive"))
    )
    (net (code "90") (name "R_INPUT7") (class "Default")
      (node (ref "C7") (pin "2") (pinfunction "2_2") (pintype "passive"))
      (node (ref "XPN7") (pin "12") (pinfunction "12_12") (pintype "passive"))
    )
    (net (code "91") (name "R_INPUT8") (class "Default")
      (node (ref "C8") (pin "2") (pinfunction "2_2") (pintype "passive"))
      (node (ref "XPN8") (pin "12") (pinfunction "12_12") (pintype "passive"))
    )
    (net (code "92") (name "SCR_BL") (class "Default")
      (node (ref "SCR") (pin "29") (pinfunction "1_29") (pintype "passive"))
      (node (ref "TEENSY_3.6") (pin "16/A2") (pinfunction "16/A2_16/A2") (pintype "bidirectional"))
    )
    (net (code "93") (name "SCR_CLK") (class "Default")
      (node (ref "SCR") (pin "24") (pinfunction "1_24") (pintype "passive"))
      (node (ref "TEENSY_3.6") (pin "13/SCK") (pinfunction "13/SCK_13/SCK") (pintype "bidirectional"))
    )
    (net (code "94") (name "SCR_CS") (class "Default")
      (node (ref "SCR") (pin "23") (pinfunction "1_23") (pintype "passive"))
      (node (ref "TEENSY_3.6") (pin "10/CS") (pinfunction "10/CS_10/CS") (pintype "bidirectional"))
    )
    (net (code "95") (name "SCR_DC") (class "Default")
      (node (ref "SCR") (pin "25") (pinfunction "1_25") (pintype "passive"))
      (node (ref "TEENSY_3.6") (pin "9/CS") (pinfunction "9/CS_9/CS") (pintype "bidirectional"))
    )
    (net (code "96") (name "SCR_MOSI") (class "Default")
      (node (ref "SCR") (pin "27") (pinfunction "1_27") (pintype "passive"))
      (node (ref "TEENSY_3.6") (pin "11/MOSI") (pinfunction "11/MOSI_11/MOSI") (pintype "bidirectional"))
    )
    (net (code "97") (name "SCR_MOSO") (class "Default")
      (node (ref "SCR") (pin "28") (pinfunction "1_28") (pintype "passive"))
      (node (ref "TEENSY_3.6") (pin "12/MISO") (pinfunction "12/MISO_12/MISO") (pintype "bidirectional"))
    )
    (net (code "98") (name "SDCLK") (class "Default")
      (node (ref "PORTBOARD") (pin "19") (pinfunction "19_19") (pintype "passive"))
      (node (ref "SDPIN5") (pin "1") (pinfunction "P_1") (pintype "passive"))
    )
    (net (code "99") (name "SDCMD") (class "Default")
      (node (ref "PORTBOARD") (pin "20") (pinfunction "20_20") (pintype "passive"))
      (node (ref "SDPIN3") (pin "1") (pinfunction "P_1") (pintype "passive"))
    )
    (net (code "100") (name "SDDATA0") (class "Default")
      (node (ref "PORTBOARD") (pin "15") (pinfunction "15_15") (pintype "passive"))
      (node (ref "SDPIN7") (pin "1") (pinfunction "P_1") (pintype "passive"))
    )
    (net (code "101") (name "SDDATA1") (class "Default")
      (node (ref "PORTBOARD") (pin "16") (pinfunction "16_16") (pintype "passive"))
      (node (ref "SDPIN8") (pin "1") (pinfunction "P_1") (pintype "passive"))
    )
    (net (code "102") (name "SDDATA2") (class "Default")
      (node (ref "PORTBOARD") (pin "17") (pinfunction "17_17") (pintype "passive"))
      (node (ref "SDPIN1") (pin "1") (pinfunction "P_1") (pintype "passive"))
    )
    (net (code "103") (name "SDDATA3") (class "Default")
      (node (ref "PORTBOARD") (pin "18") (pinfunction "18_18") (pintype "passive"))
      (node (ref "SDPIN2") (pin "1") (pinfunction "P_1") (pintype "passive"))
    )
    (net (code "104") (name "TEENSY_L") (class "Default")
      (node (ref "C18") (pin "2") (pinfunction "2_2") (pintype "passive"))
      (node (ref "TEENSY_3.6") (pin "21/DAC0") (pinfunction "A21/DAC0_21/DAC0") (pintype "bidirectional"))
    )
    (net (code "105") (name "TEENSY_R") (class "Default")
      (node (ref "C9") (pin "2") (pinfunction "2_2") (pintype "passive"))
      (node (ref "TEENSY_3.6") (pin "A22/DAC1") (pinfunction "A22/DAC1_A22/DAC1") (pintype "bidirectional"))
    )
    (net (code "106") (name "USBDATA+") (class "Default")
      (node (ref "PORTBOARD") (pin "13") (pinfunction "13_13") (pintype "passive"))
      (node (ref "USBPIN+") (pin "1") (pinfunction "P_1") (pintype "passive"))
    )
    (net (code "107") (name "USBDATA-") (class "Default")
      (node (ref "PORTBOARD") (pin "14") (pinfunction "14_14") (pintype "passive"))
      (node (ref "USBPIN-") (pin "1") (pinfunction "P_1") (pintype "passive"))
    )
    (net (code "108") (name "XPN_CLK") (class "Default")
      (node (ref "TEENSY_3.6") (pin "20/A6") (pinfunction "20/A6_20/A6") (pintype "bidirectional"))
      (node (ref "XPN1") (pin "4") (pinfunction "4_4") (pintype "passive"))
      (node (ref "XPN2") (pin "4") (pinfunction "4_4") (pintype "passive"))
      (node (ref "XPN3") (pin "4") (pinfunction "4_4") (pintype "passive"))
      (node (ref "XPN4") (pin "4") (pinfunction "4_4") (pintype "passive"))
      (node (ref "XPN5") (pin "4") (pinfunction "4_4") (pintype "passive"))
      (node (ref "XPN6") (pin "4") (pinfunction "4_4") (pintype "passive"))
      (node (ref "XPN7") (pin "4") (pinfunction "4_4") (pintype "passive"))
      (node (ref "XPN8") (pin "4") (pinfunction "4_4") (pintype "passive"))
    )
    (net (code "109") (name "XPN_CS1") (class "Default")
      (node (ref "TEENSY_3.6") (pin "6") (pinfunction "6_6") (pintype "bidirectional"))
      (node (ref "XPN1") (pin "10") (pinfunction "10_10") (pintype "passive"))
    )
    (net (code "110") (name "XPN_CS2") (class "Default")
      (node (ref "TEENSY_3.6") (pin "24") (pinfunction "24_24") (pintype "bidirectional"))
      (node (ref "XPN2") (pin "10") (pinfunction "10_10") (pintype "passive"))
    )
    (net (code "111") (name "XPN_CS3") (class "Default")
      (node (ref "TEENSY_3.6") (pin "25") (pinfunction "25_25") (pintype "bidirectional"))
      (node (ref "XPN3") (pin "10") (pinfunction "10_10") (pintype "passive"))
    )
    (net (code "112") (name "XPN_CS4") (class "Default")
      (node (ref "TEENSY_3.6") (pin "26") (pinfunction "26_26") (pintype "bidirectional"))
      (node (ref "XPN4") (pin "10") (pinfunction "10_10") (pintype "passive"))
    )
    (net (code "113") (name "XPN_CS5") (class "Default")
      (node (ref "TEENSY_3.6") (pin "27") (pinfunction "27_27") (pintype "bidirectional"))
      (node (ref "XPN5") (pin "10") (pinfunction "10_10") (pintype "passive"))
    )
    (net (code "114") (name "XPN_CS6") (class "Default")
      (node (ref "TEENSY_3.6") (pin "15/A1") (pinfunction "15/A1_15/A1") (pintype "bidirectional"))
      (node (ref "XPN6") (pin "10") (pinfunction "10_10") (pintype "passive"))
    )
    (net (code "115") (name "XPN_CS7") (class "Default")
      (node (ref "TEENSY_3.6") (pin "14/A0") (pinfunction "14/A0_14/A0") (pintype "bidirectional"))
      (node (ref "XPN7") (pin "10") (pinfunction "10_10") (pintype "passive"))
    )
    (net (code "116") (name "XPN_CS8") (class "Default")
      (node (ref "TEENSY_3.6") (pin "22/A8") (pinfunction "22/A8_22/A8") (pintype "bidirectional"))
      (node (ref "XPN8") (pin "10") (pinfunction "10_10") (pintype "passive"))
    )
    (net (code "117") (name "XPN_MISO") (class "Default")
      (node (ref "TEENSY_3.6") (pin "5") (pinfunction "5_5") (pintype "bidirectional"))
      (node (ref "XPN1") (pin "8") (pinfunction "8_8") (pintype "passive"))
      (node (ref "XPN2") (pin "8") (pinfunction "8_8") (pintype "passive"))
      (node (ref "XPN3") (pin "8") (pinfunction "8_8") (pintype "passive"))
      (node (ref "XPN4") (pin "8") (pinfunction "8_8") (pintype "passive"))
      (node (ref "XPN5") (pin "8") (pinfunction "8_8") (pintype "passive"))
      (node (ref "XPN6") (pin "8") (pinfunction "8_8") (pintype "passive"))
      (node (ref "XPN7") (pin "8") (pinfunction "8_8") (pintype "passive"))
      (node (ref "XPN8") (pin "8") (pinfunction "8_8") (pintype "passive"))
    )
    (net (code "118") (name "XPN_MOSI") (class "Default")
      (node (ref "TEENSY_3.6") (pin "21/A7") (pinfunction "21/A7_21/A7") (pintype "bidirectional"))
      (node (ref "XPN1") (pin "6") (pinfunction "6_6") (pintype "passive"))
      (node (ref "XPN2") (pin "6") (pinfunction "6_6") (pintype "passive"))
      (node (ref "XPN3") (pin "6") (pinfunction "6_6") (pintype "passive"))
      (node (ref "XPN4") (pin "6") (pinfunction "6_6") (pintype "passive"))
      (node (ref "XPN5") (pin "6") (pinfunction "6_6") (pintype "passive"))
      (node (ref "XPN6") (pin "6") (pinfunction "6_6") (pintype "passive"))
      (node (ref "XPN7") (pin "6") (pinfunction "6_6") (pintype "passive"))
      (node (ref "XPN8") (pin "6") (pinfunction "6_6") (pintype "passive"))
    )
    (net (code "119") (name "unconnected-(BUTTONS-Pad8)") (class "Default")
      (node (ref "BUTTONS") (pin "8") (pinfunction "8_8") (pintype "passive"))
    )
    (net (code "120") (name "unconnected-(J1-Pad2)") (class "Default")
      (node (ref "J1") (pin "2") (pinfunction "2_2") (pintype "passive"))
    )
    (net (code "121") (name "unconnected-(KNOBBOARD-Pad12)") (class "Default")
      (node (ref "KNOBBOARD") (pin "12") (pinfunction "12_12") (pintype "passive"))
    )
    (net (code "122") (name "unconnected-(PORTBOARD-Pad21)") (class "Default")
      (node (ref "PORTBOARD") (pin "21") (pinfunction "21_21") (pintype "passive"))
    )
    (net (code "123") (name "unconnected-(PORTBOARD-Pad22)") (class "Default")
      (node (ref "PORTBOARD") (pin "22") (pinfunction "22_22") (pintype "passive"))
    )
    (net (code "124") (name "unconnected-(SCRAA-1-Pad33)") (class "Default")
      (node (ref "SCR") (pin "33") (pinfunction "1_33") (pintype "passive"))
    )
    (net (code "125") (name "unconnected-(SCRAB-1-Pad34)") (class "Default")
      (node (ref "SCR") (pin "34") (pinfunction "1_34") (pintype "passive"))
    )
    (net (code "126") (name "unconnected-(SCRAC-1-Pad35)") (class "Default")
      (node (ref "SCR") (pin "35") (pinfunction "1_35") (pintype "passive"))
    )
    (net (code "127") (name "unconnected-(SCRAD-1-Pad36)") (class "Default")
      (node (ref "SCR") (pin "36") (pinfunction "1_36") (pintype "passive"))
    )
    (net (code "128") (name "unconnected-(SCRAE-1-Pad37)") (class "Default")
      (node (ref "SCR") (pin "37") (pinfunction "1_37") (pintype "passive"))
    )
    (net (code "129") (name "unconnected-(SCRAF-1-Pad38)") (class "Default")
      (node (ref "SCR") (pin "38") (pinfunction "1_38") (pintype "passive"))
    )
    (net (code "130") (name "unconnected-(SCRAG-1-Pad39)") (class "Default")
      (node (ref "SCR") (pin "39") (pinfunction "1_39") (pintype "passive"))
    )
    (net (code "131") (name "unconnected-(SCRAH-1-Pad4)") (class "Default")
      (node (ref "SCR") (pin "4") (pinfunction "1_4") (pintype "passive"))
    )
    (net (code "132") (name "unconnected-(SCRAI-1-Pad40)") (class "Default")
      (node (ref "SCR") (pin "40") (pinfunction "1_40") (pintype "passive"))
    )
    (net (code "133") (name "unconnected-(SCRAJ-1-Pad5)") (class "Default")
      (node (ref "SCR") (pin "5") (pinfunction "1_5") (pintype "passive"))
    )
    (net (code "134") (name "unconnected-(SCRAK-1-Pad6)") (class "Default")
      (node (ref "SCR") (pin "6") (pinfunction "1_6") (pintype "passive"))
    )
    (net (code "135") (name "unconnected-(SCRAL-1-Pad7)") (class "Default")
      (node (ref "SCR") (pin "7") (pinfunction "1_7") (pintype "passive"))
    )
    (net (code "136") (name "unconnected-(SCRAM-1-Pad8)") (class "Default")
      (node (ref "SCR") (pin "8") (pinfunction "1_8") (pintype "passive"))
    )
    (net (code "137") (name "unconnected-(SCRAN-1-Pad9)") (class "Default")
      (node (ref "SCR") (pin "9") (pinfunction "1_9") (pintype "passive"))
    )
    (net (code "138") (name "unconnected-(SCRB-1-Pad10)") (class "Default")
      (node (ref "SCR") (pin "10") (pinfunction "1_10") (pintype "passive"))
    )
    (net (code "139") (name "unconnected-(SCRC-1-Pad11)") (class "Default")
      (node (ref "SCR") (pin "11") (pinfunction "1_11") (pintype "passive"))
    )
    (net (code "140") (name "unconnected-(SCRD-1-Pad12)") (class "Default")
      (node (ref "SCR") (pin "12") (pinfunction "1_12") (pintype "passive"))
    )
    (net (code "141") (name "unconnected-(SCRE-1-Pad13)") (class "Default")
      (node (ref "SCR") (pin "13") (pinfunction "1_13") (pintype "passive"))
    )
    (net (code "142") (name "unconnected-(SCRF-1-Pad14)") (class "Default")
      (node (ref "SCR") (pin "14") (pinfunction "1_14") (pintype "passive"))
    )
    (net (code "143") (name "unconnected-(SCRG-1-Pad15)") (class "Default")
      (node (ref "SCR") (pin "15") (pinfunction "1_15") (pintype "passive"))
    )
    (net (code "144") (name "unconnected-(SCRH-1-Pad16)") (class "Default")
      (node (ref "SCR") (pin "16") (pinfunction "1_16") (pintype "passive"))
    )
    (net (code "145") (name "unconnected-(SCRI-1-Pad17)") (class "Default")
      (node (ref "SCR") (pin "17") (pinfunction "1_17") (pintype "passive"))
    )
    (net (code "146") (name "unconnected-(SCRJ-1-Pad18)") (class "Default")
      (node (ref "SCR") (pin "18") (pinfunction "1_18") (pintype "passive"))
    )
    (net (code "147") (name "unconnected-(SCRK-1-Pad19)") (class "Default")
      (node (ref "SCR") (pin "19") (pinfunction "1_19") (pintype "passive"))
    )
    (net (code "148") (name "unconnected-(SCRM-1-Pad20)") (class "Default")
      (node (ref "SCR") (pin "20") (pinfunction "1_20") (pintype "passive"))
    )
    (net (code "149") (name "unconnected-(SCRN-1-Pad21)") (class "Default")
      (node (ref "SCR") (pin "21") (pinfunction "1_21") (pintype "passive"))
    )
    (net (code "150") (name "unconnected-(SCRO-1-Pad22)") (class "Default")
      (node (ref "SCR") (pin "22") (pinfunction "1_22") (pintype "passive"))
    )
    (net (code "151") (name "unconnected-(SCRS-1-Pad26)") (class "Default")
      (node (ref "SCR") (pin "26") (pinfunction "1_26") (pintype "passive"))
    )
    (net (code "152") (name "unconnected-(SCRW-1-Pad3)") (class "Default")
      (node (ref "SCR") (pin "3") (pinfunction "1_3") (pintype "passive"))
    )
    (net (code "153") (name "unconnected-(SCRX-1-Pad30)") (class "Default")
      (node (ref "SCR") (pin "30") (pinfunction "1_30") (pintype "passive"))
    )
    (net (code "154") (name "unconnected-(SCRY-1-Pad31)") (class "Default")
      (node (ref "SCR") (pin "31") (pinfunction "1_31") (pintype "passive"))
    )
    (net (code "155") (name "unconnected-(SCRZ-1-Pad32)") (class "Default")
      (node (ref "SCR") (pin "32") (pinfunction "1_32") (pintype "passive"))
    )
    (net (code "156") (name "unconnected-(TEENSY_3.6-Pad3V3_2)") (class "Default")
      (node (ref "TEENSY_3.6") (pin "3V3_2") (pinfunction "3V3_2_3V3_2") (pintype "bidirectional"))
    )
    (net (code "157") (name "unconnected-(TEENSY_3.6-Pad3V3_LO)") (class "Default")
      (node (ref "TEENSY_3.6") (pin "3V3_LO") (pinfunction "3V3_LO_3V3_LO") (pintype "bidirectional"))
    )
    (net (code "158") (name "unconnected-(TEENSY_3.6-PadA11)") (class "Default")
      (node (ref "TEENSY_3.6") (pin "A11") (pinfunction "A11_A11") (pintype "bidirectional"))
    )
    (net (code "159") (name "unconnected-(TEENSY_3.6-PadAGND)") (class "Default")
      (node (ref "TEENSY_3.6") (pin "AGND") (pinfunction "AGND_AGND") (pintype "bidirectional"))
    )
    (net (code "160") (name "unconnected-(TEENSY_3.6-PadAREF)") (class "Default")
      (node (ref "TEENSY_3.6") (pin "AREF") (pinfunction "AREF_AREF") (pintype "bidirectional"))
    )
    (net (code "161") (name "unconnected-(TEENSY_3.6-PadGND2)") (class "Default")
      (node (ref "TEENSY_3.6") (pin "GND2") (pinfunction "GND2_GND2") (pintype "bidirectional"))
    )
    (net (code "162") (name "unconnected-(TEENSY_3.6-PadGND3)") (class "Default")
      (node (ref "TEENSY_3.6") (pin "GND3") (pinfunction "GND3_GND3") (pintype "bidirectional"))
    )
    (net (code "163") (name "unconnected-(TEENSY_3.6-PadPROG)") (class "Default")
      (node (ref "TEENSY_3.6") (pin "PROG") (pinfunction "PROG_PROG") (pintype "bidirectional"))
    )
    (net (code "164") (name "unconnected-(TEENSY_3.6-PadRESET)") (class "Default")
      (node (ref "TEENSY_3.6") (pin "RESET") (pinfunction "RESET_RESET") (pintype "bidirectional"))
    )
    (net (code "165") (name "unconnected-(TEENSY_3.6-PadU5V)") (class "Default")
      (node (ref "TEENSY_3.6") (pin "U5V") (pinfunction "U5V_U5V") (pintype "bidirectional"))
    )
    (net (code "166") (name "unconnected-(TEENSY_3.6-PadUD+)") (class "Default")
      (node (ref "TEENSY_3.6") (pin "UD+") (pinfunction "UD+_UD+") (pintype "bidirectional"))
    )
    (net (code "167") (name "unconnected-(TEENSY_3.6-PadUD-)") (class "Default")
      (node (ref "TEENSY_3.6") (pin "UD-") (pinfunction "UD-_UD-") (pintype "bidirectional"))
    )
    (net (code "168") (name "unconnected-(TEENSY_3.6-PadUGND1)") (class "Default")
      (node (ref "TEENSY_3.6") (pin "UGND1") (pinfunction "UGND1_UGND1") (pintype "bidirectional"))
    )
    (net (code "169") (name "unconnected-(TEENSY_3.6-PadUGND2)") (class "Default")
      (node (ref "TEENSY_3.6") (pin "UGND2") (pinfunction "UGND2_UGND2") (pintype "bidirectional"))
    )
    (net (code "170") (name "unconnected-(TEENSY_3.6-PadVBAT)") (class "Default")
      (node (ref "TEENSY_3.6") (pin "VBAT") (pinfunction "VBAT_VBAT") (pintype "bidirectional"))
    )
    (net (code "171") (name "unconnected-(TEENSY_3.6-PadVUSB)") (class "Default")
      (node (ref "TEENSY_3.6") (pin "VUSB") (pinfunction "VUSB_VUSB") (pintype "bidirectional"))
    )
    (net (code "172") (name "unconnected-(XPN1-Pad2)") (class "Default")
      (node (ref "XPN1") (pin "2") (pinfunction "2_2") (pintype "passive"))
    )
    (net (code "173") (name "unconnected-(XPN1-Pad3)") (class "Default")
      (node (ref "XPN1") (pin "3") (pinfunction "3_3") (pintype "passive"))
    )
    (net (code "174") (name "unconnected-(XPN2-Pad2)") (class "Default")
      (node (ref "XPN2") (pin "2") (pinfunction "2_2") (pintype "passive"))
    )
    (net (code "175") (name "unconnected-(XPN2-Pad3)") (class "Default")
      (node (ref "XPN2") (pin "3") (pinfunction "3_3") (pintype "passive"))
    )
    (net (code "176") (name "unconnected-(XPN3-Pad2)") (class "Default")
      (node (ref "XPN3") (pin "2") (pinfunction "2_2") (pintype "passive"))
    )
    (net (code "177") (name "unconnected-(XPN3-Pad3)") (class "Default")
      (node (ref "XPN3") (pin "3") (pinfunction "3_3") (pintype "passive"))
    )
    (net (code "178") (name "unconnected-(XPN4-Pad2)") (class "Default")
      (node (ref "XPN4") (pin "2") (pinfunction "2_2") (pintype "passive"))
    )
    (net (code "179") (name "unconnected-(XPN4-Pad3)") (class "Default")
      (node (ref "XPN4") (pin "3") (pinfunction "3_3") (pintype "passive"))
    )
    (net (code "180") (name "unconnected-(XPN5-Pad2)") (class "Default")
      (node (ref "XPN5") (pin "2") (pinfunction "2_2") (pintype "passive"))
    )
    (net (code "181") (name "unconnected-(XPN5-Pad3)") (class "Default")
      (node (ref "XPN5") (pin "3") (pinfunction "3_3") (pintype "passive"))
    )
    (net (code "182") (name "unconnected-(XPN6-Pad2)") (class "Default")
      (node (ref "XPN6") (pin "2") (pinfunction "2_2") (pintype "passive"))
    )
    (net (code "183") (name "unconnected-(XPN6-Pad3)") (class "Default")
      (node (ref "XPN6") (pin "3") (pinfunction "3_3") (pintype "passive"))
    )
    (net (code "184") (name "unconnected-(XPN7-Pad2)") (class "Default")
      (node (ref "XPN7") (pin "2") (pinfunction "2_2") (pintype "passive"))
    )
    (net (code "185") (name "unconnected-(XPN7-Pad3)") (class "Default")
      (node (ref "XPN7") (pin "3") (pinfunction "3_3") (pintype "passive"))
    )
    (net (code "186") (name "unconnected-(XPN8-Pad2)") (class "Default")
      (node (ref "XPN8") (pin "2") (pinfunction "2_2") (pintype "passive"))
    )
    (net (code "187") (name "unconnected-(XPN8-Pad3)") (class "Default")
      (node (ref "XPN8") (pin "3") (pinfunction "3_3") (pintype "passive"))
    )
  )
)
